# PAYL0003_PC_Memory.net
KiCad netlist of a schematic drawn in Altium Designer
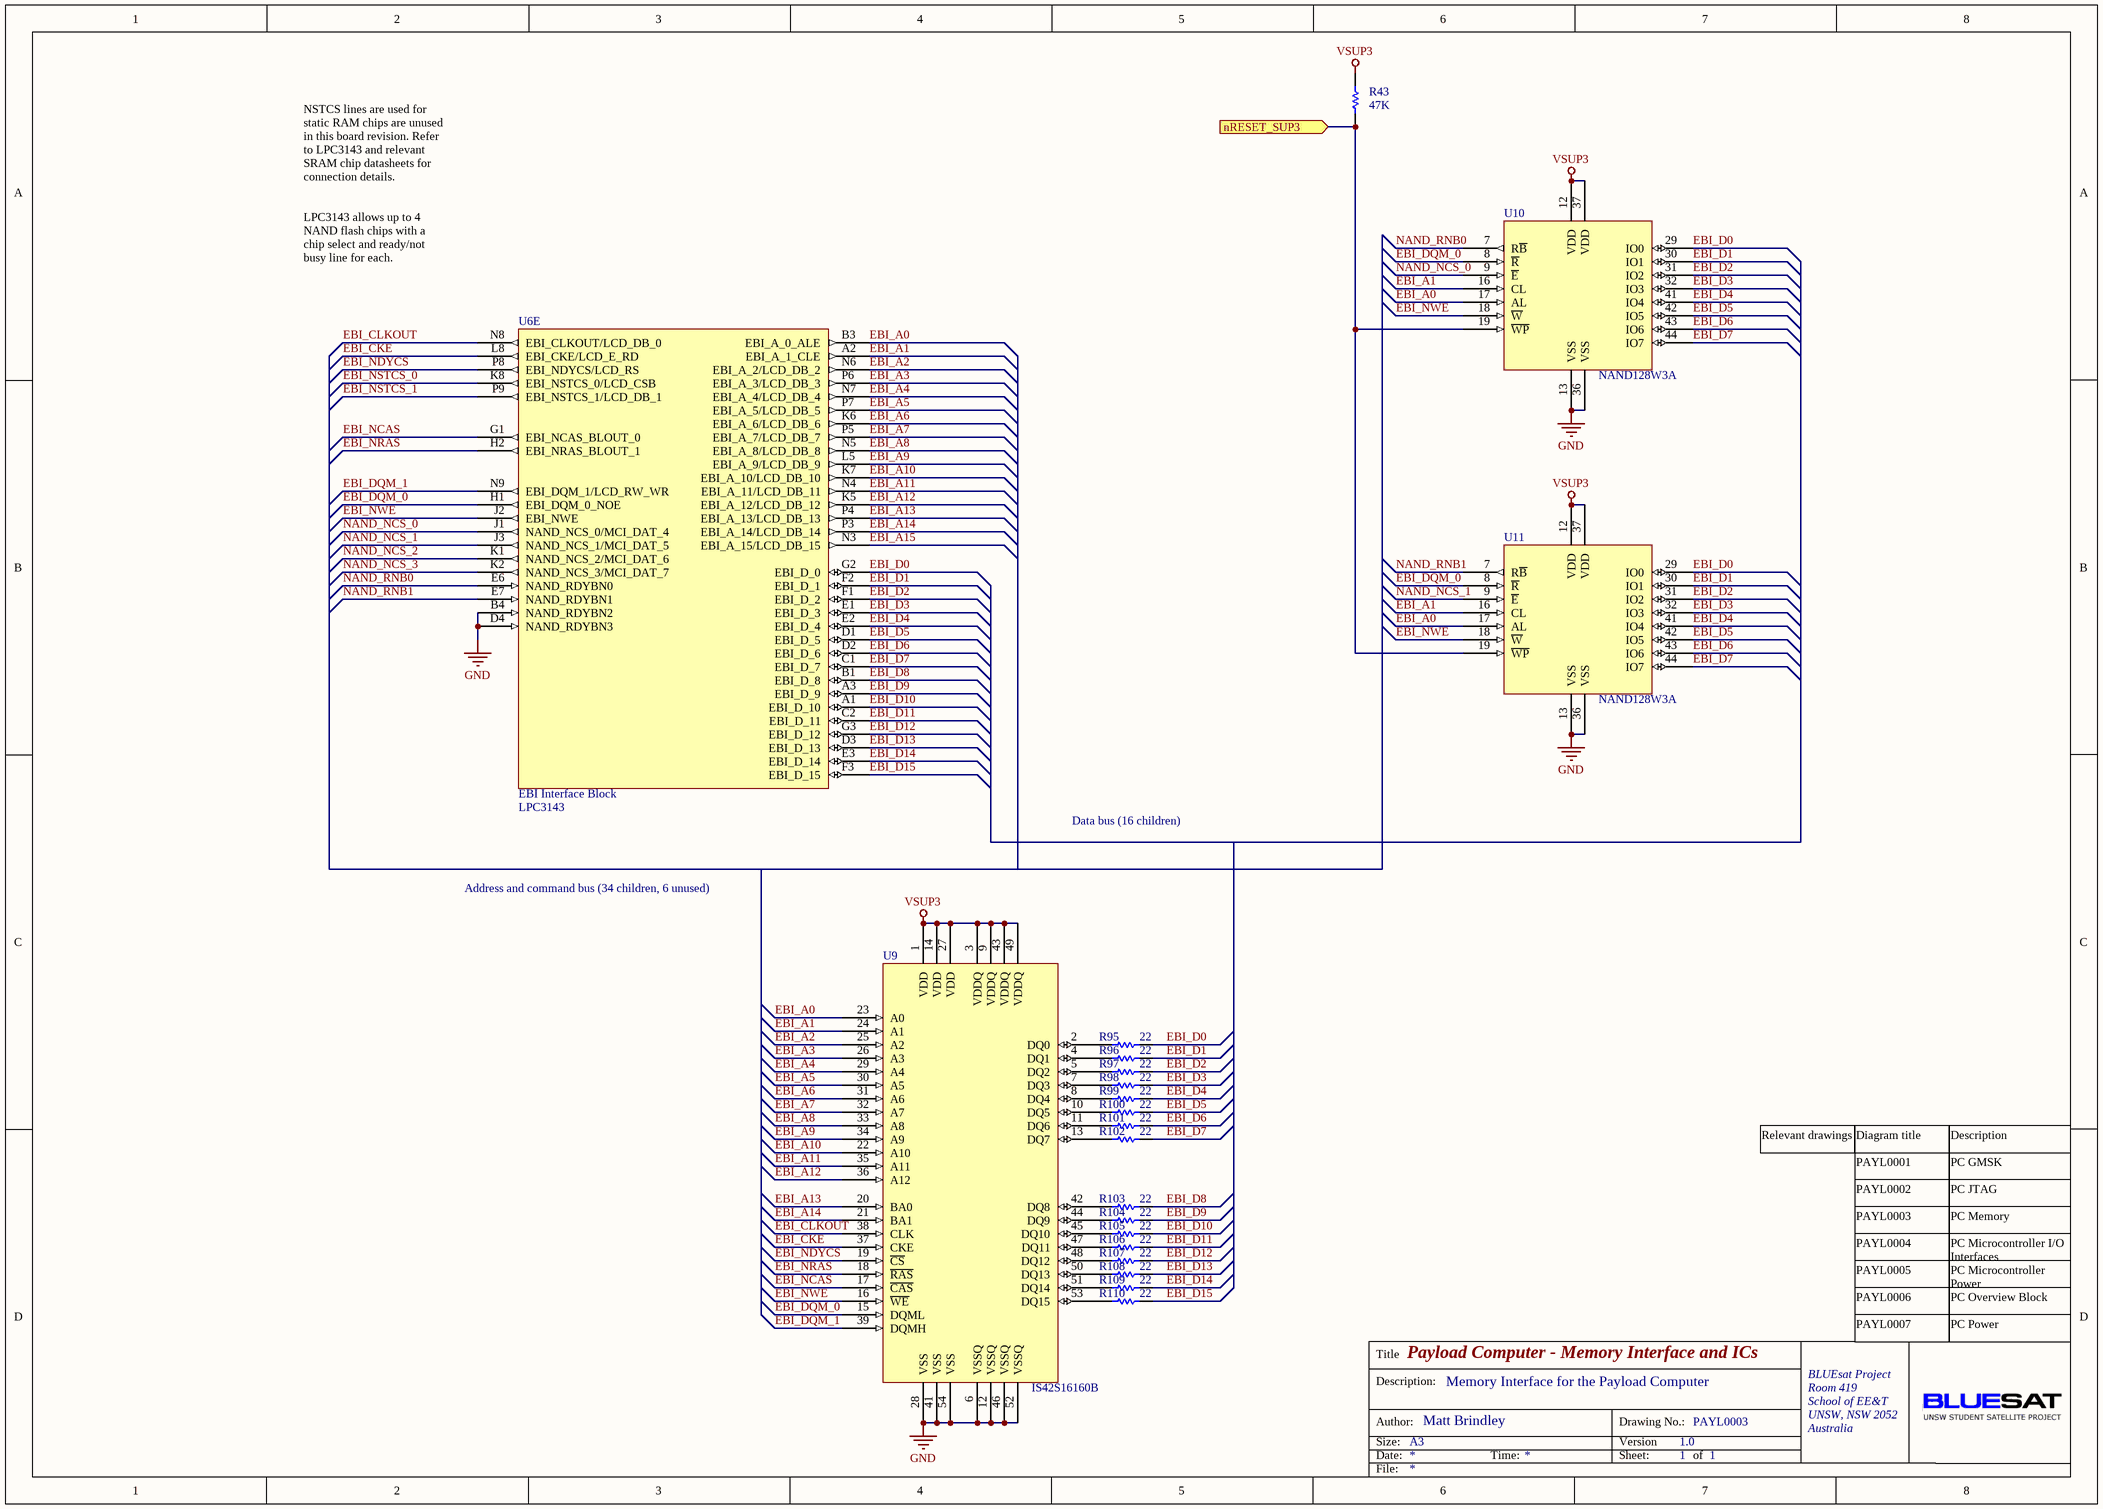
[diagram p0: PAYL0003_PC_Memory.SchDoc]

(export (version "E")
  (design (tool "Eeschema 10.0.6"))
  (components
    (comp (ref "R43")
      (value "47K")
      (footprint "6-0805_L")
      (description "Semiconductor Resistor")
      (fields (field (name "Comment") "Res Semi") (field (name "PUBLISHER") "Altium Limited"))
      (libsource (lib "Miscellaneous Devices") (part "Res Semi"))
    )
    (comp (ref "R95")
      (value "22")
      (footprint "6-0805_L")
      (description "Semiconductor Resistor")
      (fields (field (name "Comment") "Res Semi") (field (name "PUBLISHER") "Altium Limited"))
      (libsource (lib "Miscellaneous Devices") (part "Res Semi"))
    )
    (comp (ref "R96")
      (value "22")
      (footprint "6-0805_L")
      (description "Semiconductor Resistor")
      (fields (field (name "Comment") "Res Semi") (field (name "PUBLISHER") "Altium Limited"))
      (libsource (lib "Miscellaneous Devices") (part "Res Semi"))
    )
    (comp (ref "R97")
      (value "22")
      (footprint "6-0805_L")
      (description "Semiconductor Resistor")
      (fields (field (name "Comment") "Res Semi") (field (name "PUBLISHER") "Altium Limited"))
      (libsource (lib "Miscellaneous Devices") (part "Res Semi"))
    )
    (comp (ref "R98")
      (value "22")
      (footprint "6-0805_L")
      (description "Semiconductor Resistor")
      (fields (field (name "Comment") "Res Semi") (field (name "PUBLISHER") "Altium Limited"))
      (libsource (lib "Miscellaneous Devices") (part "Res Semi"))
    )
    (comp (ref "R99")
      (value "22")
      (footprint "6-0805_L")
      (description "Semiconductor Resistor")
      (fields (field (name "Comment") "Res Semi") (field (name "PUBLISHER") "Altium Limited"))
      (libsource (lib "Miscellaneous Devices") (part "Res Semi"))
    )
    (comp (ref "R100")
      (value "22")
      (footprint "6-0805_L")
      (description "Semiconductor Resistor")
      (fields (field (name "Comment") "Res Semi") (field (name "PUBLISHER") "Altium Limited"))
      (libsource (lib "Miscellaneous Devices") (part "Res Semi"))
    )
    (comp (ref "R101")
      (value "22")
      (footprint "6-0805_L")
      (description "Semiconductor Resistor")
      (fields (field (name "Comment") "Res Semi") (field (name "PUBLISHER") "Altium Limited"))
      (libsource (lib "Miscellaneous Devices") (part "Res Semi"))
    )
    (comp (ref "R102")
      (value "22")
      (footprint "6-0805_L")
      (description "Semiconductor Resistor")
      (fields (field (name "Comment") "Res Semi") (field (name "PUBLISHER") "Altium Limited"))
      (libsource (lib "Miscellaneous Devices") (part "Res Semi"))
    )
    (comp (ref "R103")
      (value "22")
      (footprint "6-0805_L")
      (description "Semiconductor Resistor")
      (fields (field (name "Comment") "Res Semi") (field (name "PUBLISHER") "Altium Limited"))
      (libsource (lib "Miscellaneous Devices") (part "Res Semi"))
    )
    (comp (ref "R104")
      (value "22")
      (footprint "6-0805_L")
      (description "Semiconductor Resistor")
      (fields (field (name "Comment") "Res Semi") (field (name "PUBLISHER") "Altium Limited"))
      (libsource (lib "Miscellaneous Devices") (part "Res Semi"))
    )
    (comp (ref "R105")
      (value "22")
      (footprint "6-0805_L")
      (description "Semiconductor Resistor")
      (fields (field (name "Comment") "Res Semi") (field (name "PUBLISHER") "Altium Limited"))
      (libsource (lib "Miscellaneous Devices") (part "Res Semi"))
    )
    (comp (ref "R106")
      (value "22")
      (footprint "6-0805_L")
      (description "Semiconductor Resistor")
      (fields (field (name "Comment") "Res Semi") (field (name "PUBLISHER") "Altium Limited"))
      (libsource (lib "Miscellaneous Devices") (part "Res Semi"))
    )
    (comp (ref "R107")
      (value "22")
      (footprint "6-0805_L")
      (description "Semiconductor Resistor")
      (fields (field (name "Comment") "Res Semi") (field (name "PUBLISHER") "Altium Limited"))
      (libsource (lib "Miscellaneous Devices") (part "Res Semi"))
    )
    (comp (ref "R108")
      (value "22")
      (footprint "6-0805_L")
      (description "Semiconductor Resistor")
      (fields (field (name "Comment") "Res Semi") (field (name "PUBLISHER") "Altium Limited"))
      (libsource (lib "Miscellaneous Devices") (part "Res Semi"))
    )
    (comp (ref "R109")
      (value "22")
      (footprint "6-0805_L")
      (description "Semiconductor Resistor")
      (fields (field (name "Comment") "Res Semi") (field (name "PUBLISHER") "Altium Limited"))
      (libsource (lib "Miscellaneous Devices") (part "Res Semi"))
    )
    (comp (ref "R110")
      (value "22")
      (footprint "6-0805_L")
      (description "Semiconductor Resistor")
      (fields (field (name "Comment") "Res Semi") (field (name "PUBLISHER") "Altium Limited"))
      (libsource (lib "Miscellaneous Devices") (part "Res Semi"))
    )
    (comp (ref "U6")
      (value "LPC3143")
      (footprint "PC_Footprints:BGA180C80P14X14_1200X1200X120")
      (description "NXP ARM9 based microcontroller")
      (fields (field (name "PUBLISHER") "BLUEsat Project"))
      (libsource (lib "PC_Components") (part "LPC3143"))
    )
    (comp (ref "U9")
      (value "IS42S16160B")
      (footprint "TSOP80P1180X120-54M")
      (description "16Mb x 16 (256Mb) Parallel Interface SDRAM")
      (fields (field (name "PUBLISHER") "Altium Limited"))
      (libsource (lib "PC_Components") (part "IS42S16160B"))
    )
    (comp (ref "U10")
      (value "NAND128W3A")
      (footprint "TSSOP50P2000X120-48M")
      (description "128Mb 8b wide NAND Flash")
      (fields (field (name "PUBLISHER") "Altium Limited"))
      (libsource (lib "PC_Components") (part "NAND128W3A"))
    )
    (comp (ref "U11")
      (value "NAND128W3A")
      (footprint "TSSOP50P2000X120-48M")
      (description "128Mb 8b wide NAND Flash")
      (fields (field (name "PUBLISHER") "Altium Limited"))
      (libsource (lib "PC_Components") (part "NAND128W3A"))
    )
  )
  (nets
    (net (code "1") (name "/EBI_A0") (class "Default")
      (node (ref "U10") (pin "17") (pinfunction "AL_17") (pintype "input"))
      (node (ref "U11") (pin "17") (pinfunction "AL_17") (pintype "input"))
      (node (ref "U6") (pin "B3") (pinfunction "EBI_A_0_ALE_B3") (pintype "output"))
      (node (ref "U9") (pin "23") (pinfunction "A0_23") (pintype "input"))
    )
    (net (code "2") (name "/EBI_A1") (class "Default")
      (node (ref "U10") (pin "16") (pinfunction "CL_16") (pintype "input"))
      (node (ref "U11") (pin "16") (pinfunction "CL_16") (pintype "input"))
      (node (ref "U6") (pin "A2") (pinfunction "EBI_A_1_CLE_A2") (pintype "output"))
      (node (ref "U9") (pin "24") (pinfunction "A1_24") (pintype "input"))
    )
    (net (code "3") (name "/EBI_A2") (class "Default")
      (node (ref "U6") (pin "N6") (pinfunction "EBI_A_2/LCD_DB_2_N6") (pintype "output"))
      (node (ref "U9") (pin "25") (pinfunction "A2_25") (pintype "input"))
    )
    (net (code "4") (name "/EBI_A3") (class "Default")
      (node (ref "U6") (pin "P6") (pinfunction "EBI_A_3/LCD_DB_3_P6") (pintype "output"))
      (node (ref "U9") (pin "26") (pinfunction "A3_26") (pintype "input"))
    )
    (net (code "5") (name "/EBI_A4") (class "Default")
      (node (ref "U6") (pin "N7") (pinfunction "EBI_A_4/LCD_DB_4_N7") (pintype "output"))
      (node (ref "U9") (pin "29") (pinfunction "A4_29") (pintype "input"))
    )
    (net (code "6") (name "/EBI_A5") (class "Default")
      (node (ref "U6") (pin "P7") (pinfunction "EBI_A_5/LCD_DB_5_P7") (pintype "output"))
      (node (ref "U9") (pin "30") (pinfunction "A5_30") (pintype "input"))
    )
    (net (code "7") (name "/EBI_A6") (class "Default")
      (node (ref "U6") (pin "K6") (pinfunction "EBI_A_6/LCD_DB_6_K6") (pintype "output"))
      (node (ref "U9") (pin "31") (pinfunction "A6_31") (pintype "input"))
    )
    (net (code "8") (name "/EBI_A7") (class "Default")
      (node (ref "U6") (pin "P5") (pinfunction "EBI_A_7/LCD_DB_7_P5") (pintype "output"))
      (node (ref "U9") (pin "32") (pinfunction "A7_32") (pintype "input"))
    )
    (net (code "9") (name "/EBI_A8") (class "Default")
      (node (ref "U6") (pin "N5") (pinfunction "EBI_A_8/LCD_DB_8_N5") (pintype "output"))
      (node (ref "U9") (pin "33") (pinfunction "A8_33") (pintype "input"))
    )
    (net (code "10") (name "/EBI_A9") (class "Default")
      (node (ref "U6") (pin "L5") (pinfunction "EBI_A_9/LCD_DB_9_L5") (pintype "output"))
      (node (ref "U9") (pin "34") (pinfunction "A9_34") (pintype "input"))
    )
    (net (code "11") (name "/EBI_A10") (class "Default")
      (node (ref "U6") (pin "K7") (pinfunction "EBI_A_10/LCD_DB_10_K7") (pintype "output"))
      (node (ref "U9") (pin "22") (pinfunction "A10_22") (pintype "input"))
    )
    (net (code "12") (name "/EBI_A11") (class "Default")
      (node (ref "U6") (pin "N4") (pinfunction "EBI_A_11/LCD_DB_11_N4") (pintype "output"))
      (node (ref "U9") (pin "35") (pinfunction "A11_35") (pintype "input"))
    )
    (net (code "13") (name "/EBI_A12") (class "Default")
      (node (ref "U6") (pin "K5") (pinfunction "EBI_A_12/LCD_DB_12_K5") (pintype "output"))
      (node (ref "U9") (pin "36") (pinfunction "A12_36") (pintype "input"))
    )
    (net (code "14") (name "/EBI_A13") (class "Default")
      (node (ref "U6") (pin "P4") (pinfunction "EBI_A_13/LCD_DB_13_P4") (pintype "output"))
      (node (ref "U9") (pin "20") (pinfunction "BA0_20") (pintype "input"))
    )
    (net (code "15") (name "/EBI_A14") (class "Default")
      (node (ref "U6") (pin "P3") (pinfunction "EBI_A_14/LCD_DB_14_P3") (pintype "output"))
      (node (ref "U9") (pin "21") (pinfunction "BA1_21") (pintype "input"))
    )
    (net (code "16") (name "/EBI_A15") (class "Default")
      (node (ref "U6") (pin "N3") (pinfunction "EBI_A_15/LCD_DB_15_N3") (pintype "output"))
    )
    (net (code "17") (name "/EBI_CKE") (class "Default")
      (node (ref "U6") (pin "L8") (pinfunction "EBI_CKE/LCD_E_RD_L8") (pintype "output"))
      (node (ref "U9") (pin "37") (pinfunction "CKE_37") (pintype "input"))
    )
    (net (code "18") (name "/EBI_CLKOUT") (class "Default")
      (node (ref "U6") (pin "N8") (pinfunction "EBI_CLKOUT/LCD_DB_0_N8") (pintype "output"))
      (node (ref "U9") (pin "38") (pinfunction "CLK_38") (pintype "input"))
    )
    (net (code "19") (name "/EBI_D0") (class "Default")
      (node (ref "R95") (pin "2") (pinfunction "2_2") (pintype "passive"))
      (node (ref "U10") (pin "29") (pinfunction "IO0_29") (pintype "bidirectional"))
      (node (ref "U11") (pin "29") (pinfunction "IO0_29") (pintype "bidirectional"))
      (node (ref "U6") (pin "G2") (pinfunction "EBI_D_0_G2") (pintype "bidirectional"))
    )
    (net (code "20") (name "/EBI_D1") (class "Default")
      (node (ref "R96") (pin "2") (pinfunction "2_2") (pintype "passive"))
      (node (ref "U10") (pin "30") (pinfunction "IO1_30") (pintype "bidirectional"))
      (node (ref "U11") (pin "30") (pinfunction "IO1_30") (pintype "bidirectional"))
      (node (ref "U6") (pin "F2") (pinfunction "EBI_D_1_F2") (pintype "bidirectional"))
    )
    (net (code "21") (name "/EBI_D2") (class "Default")
      (node (ref "R97") (pin "2") (pinfunction "2_2") (pintype "passive"))
      (node (ref "U10") (pin "31") (pinfunction "IO2_31") (pintype "bidirectional"))
      (node (ref "U11") (pin "31") (pinfunction "IO2_31") (pintype "bidirectional"))
      (node (ref "U6") (pin "F1") (pinfunction "EBI_D_2_F1") (pintype "bidirectional"))
    )
    (net (code "22") (name "/EBI_D3") (class "Default")
      (node (ref "R98") (pin "2") (pinfunction "2_2") (pintype "passive"))
      (node (ref "U10") (pin "32") (pinfunction "IO3_32") (pintype "bidirectional"))
      (node (ref "U11") (pin "32") (pinfunction "IO3_32") (pintype "bidirectional"))
      (node (ref "U6") (pin "E1") (pinfunction "EBI_D_3_E1") (pintype "bidirectional"))
    )
    (net (code "23") (name "/EBI_D4") (class "Default")
      (node (ref "R99") (pin "2") (pinfunction "2_2") (pintype "passive"))
      (node (ref "U10") (pin "41") (pinfunction "IO4_41") (pintype "bidirectional"))
      (node (ref "U11") (pin "41") (pinfunction "IO4_41") (pintype "bidirectional"))
      (node (ref "U6") (pin "E2") (pinfunction "EBI_D_4_E2") (pintype "bidirectional"))
    )
    (net (code "24") (name "/EBI_D5") (class "Default")
      (node (ref "R100") (pin "2") (pinfunction "2_2") (pintype "passive"))
      (node (ref "U10") (pin "42") (pinfunction "IO5_42") (pintype "bidirectional"))
      (node (ref "U11") (pin "42") (pinfunction "IO5_42") (pintype "bidirectional"))
      (node (ref "U6") (pin "D1") (pinfunction "EBI_D_5_D1") (pintype "bidirectional"))
    )
    (net (code "25") (name "/EBI_D6") (class "Default")
      (node (ref "R101") (pin "2") (pinfunction "2_2") (pintype "passive"))
      (node (ref "U10") (pin "43") (pinfunction "IO6_43") (pintype "bidirectional"))
      (node (ref "U11") (pin "43") (pinfunction "IO6_43") (pintype "bidirectional"))
      (node (ref "U6") (pin "D2") (pinfunction "EBI_D_6_D2") (pintype "bidirectional"))
    )
    (net (code "26") (name "/EBI_D7") (class "Default")
      (node (ref "R102") (pin "2") (pinfunction "2_2") (pintype "passive"))
      (node (ref "U10") (pin "44") (pinfunction "IO7_44") (pintype "bidirectional"))
      (node (ref "U11") (pin "44") (pinfunction "IO7_44") (pintype "bidirectional"))
      (node (ref "U6") (pin "C1") (pinfunction "EBI_D_7_C1") (pintype "bidirectional"))
    )
    (net (code "27") (name "/EBI_D8") (class "Default")
      (node (ref "R103") (pin "2") (pinfunction "2_2") (pintype "passive"))
      (node (ref "U6") (pin "B1") (pinfunction "EBI_D_8_B1") (pintype "bidirectional"))
    )
    (net (code "28") (name "/EBI_D9") (class "Default")
      (node (ref "R104") (pin "2") (pinfunction "2_2") (pintype "passive"))
      (node (ref "U6") (pin "A3") (pinfunction "EBI_D_9_A3") (pintype "bidirectional"))
    )
    (net (code "29") (name "/EBI_D10") (class "Default")
      (node (ref "R105") (pin "2") (pinfunction "2_2") (pintype "passive"))
      (node (ref "U6") (pin "A1") (pinfunction "EBI_D_10_A1") (pintype "bidirectional"))
    )
    (net (code "30") (name "/EBI_D11") (class "Default")
      (node (ref "R106") (pin "2") (pinfunction "2_2") (pintype "passive"))
      (node (ref "U6") (pin "C2") (pinfunction "EBI_D_11_C2") (pintype "bidirectional"))
    )
    (net (code "31") (name "/EBI_D12") (class "Default")
      (node (ref "R107") (pin "2") (pinfunction "2_2") (pintype "passive"))
      (node (ref "U6") (pin "G3") (pinfunction "EBI_D_12_G3") (pintype "bidirectional"))
    )
    (net (code "32") (name "/EBI_D13") (class "Default")
      (node (ref "R108") (pin "2") (pinfunction "2_2") (pintype "passive"))
      (node (ref "U6") (pin "D3") (pinfunction "EBI_D_13_D3") (pintype "bidirectional"))
    )
    (net (code "33") (name "/EBI_D14") (class "Default")
      (node (ref "R109") (pin "2") (pinfunction "2_2") (pintype "passive"))
      (node (ref "U6") (pin "E3") (pinfunction "EBI_D_14_E3") (pintype "bidirectional"))
    )
    (net (code "34") (name "/EBI_D15") (class "Default")
      (node (ref "R110") (pin "2") (pinfunction "2_2") (pintype "passive"))
      (node (ref "U6") (pin "F3") (pinfunction "EBI_D_15_F3") (pintype "bidirectional"))
    )
    (net (code "35") (name "/EBI_DQM_0") (class "Default")
      (node (ref "U10") (pin "8") (pinfunction "~{R}_8") (pintype "input"))
      (node (ref "U11") (pin "8") (pinfunction "~{R}_8") (pintype "input"))
      (node (ref "U6") (pin "H1") (pinfunction "EBI_DQM_0_NOE_H1") (pintype "output"))
      (node (ref "U9") (pin "15") (pinfunction "DQML_15") (pintype "input"))
    )
    (net (code "36") (name "/EBI_DQM_1") (class "Default")
      (node (ref "U6") (pin "N9") (pinfunction "EBI_DQM_1/LCD_RW_WR_N9") (pintype "output"))
      (node (ref "U9") (pin "39") (pinfunction "DQMH_39") (pintype "input"))
    )
    (net (code "37") (name "/EBI_NCAS") (class "Default")
      (node (ref "U6") (pin "G1") (pinfunction "EBI_NCAS_BLOUT_0_G1") (pintype "output"))
      (node (ref "U9") (pin "17") (pinfunction "~{CAS}_17") (pintype "input"))
    )
    (net (code "38") (name "/EBI_NDYCS") (class "Default")
      (node (ref "U6") (pin "P8") (pinfunction "EBI_NDYCS/LCD_RS_P8") (pintype "output"))
      (node (ref "U9") (pin "19") (pinfunction "~{CS}_19") (pintype "input"))
    )
    (net (code "39") (name "/EBI_NRAS") (class "Default")
      (node (ref "U6") (pin "H2") (pinfunction "EBI_NRAS_BLOUT_1_H2") (pintype "output"))
      (node (ref "U9") (pin "18") (pinfunction "~{RAS}_18") (pintype "input"))
    )
    (net (code "40") (name "/EBI_NSTCS_0") (class "Default")
      (node (ref "U6") (pin "K8") (pinfunction "EBI_NSTCS_0/LCD_CSB_K8") (pintype "output"))
    )
    (net (code "41") (name "/EBI_NSTCS_1") (class "Default")
      (node (ref "U6") (pin "P9") (pinfunction "EBI_NSTCS_1/LCD_DB_1_P9") (pintype "output"))
    )
    (net (code "42") (name "/EBI_NWE") (class "Default")
      (node (ref "U10") (pin "18") (pinfunction "~{W}_18") (pintype "input"))
      (node (ref "U11") (pin "18") (pinfunction "~{W}_18") (pintype "input"))
      (node (ref "U6") (pin "J2") (pinfunction "EBI_NWE_J2") (pintype "output"))
      (node (ref "U9") (pin "16") (pinfunction "~{WE}_16") (pintype "input"))
    )
    (net (code "43") (name "/NAND_NCS_0") (class "Default")
      (node (ref "U10") (pin "9") (pinfunction "~{E}_9") (pintype "input"))
      (node (ref "U6") (pin "J1") (pinfunction "NAND_NCS_0/MCI_DAT_4_J1") (pintype "output"))
    )
    (net (code "44") (name "/NAND_NCS_1") (class "Default")
      (node (ref "U11") (pin "9") (pinfunction "~{E}_9") (pintype "input"))
      (node (ref "U6") (pin "J3") (pinfunction "NAND_NCS_1/MCI_DAT_5_J3") (pintype "output"))
    )
    (net (code "45") (name "/NAND_NCS_2") (class "Default")
      (node (ref "U6") (pin "K1") (pinfunction "NAND_NCS_2/MCI_DAT_6_K1") (pintype "output"))
    )
    (net (code "46") (name "/NAND_NCS_3") (class "Default")
      (node (ref "U6") (pin "K2") (pinfunction "NAND_NCS_3/MCI_DAT_7_K2") (pintype "output"))
    )
    (net (code "47") (name "/NAND_RNB0") (class "Default")
      (node (ref "U10") (pin "7") (pinfunction "R~{B}_7") (pintype "output"))
      (node (ref "U6") (pin "E6") (pinfunction "NAND_RDYBN0_E6") (pintype "input"))
    )
    (net (code "48") (name "/NAND_RNB1") (class "Default")
      (node (ref "U11") (pin "7") (pinfunction "R~{B}_7") (pintype "output"))
      (node (ref "U6") (pin "E7") (pinfunction "NAND_RDYBN1_E7") (pintype "input"))
    )
    (net (code "49") (name "/nRESET_SUP3") (class "Default")
      (node (ref "R43") (pin "1") (pinfunction "1_1") (pintype "passive"))
      (node (ref "U10") (pin "19") (pinfunction "~{WP}_19") (pintype "input"))
      (node (ref "U11") (pin "19") (pinfunction "~{WP}_19") (pintype "input"))
    )
    (net (code "50") (name "GND") (class "Default")
      (node (ref "U10") (pin "13") (pinfunction "VSS_13") (pintype "power_in"))
      (node (ref "U10") (pin "36") (pinfunction "VSS_36") (pintype "power_in"))
      (node (ref "U11") (pin "13") (pinfunction "VSS_13") (pintype "power_in"))
      (node (ref "U11") (pin "36") (pinfunction "VSS_36") (pintype "power_in"))
      (node (ref "U6") (pin "B4") (pinfunction "NAND_RDYBN2_B4") (pintype "input"))
      (node (ref "U6") (pin "D4") (pinfunction "NAND_RDYBN3_D4") (pintype "input"))
      (node (ref "U9") (pin "12") (pinfunction "VSSQ_12") (pintype "power_in"))
      (node (ref "U9") (pin "28") (pinfunction "VSS_28") (pintype "power_in"))
      (node (ref "U9") (pin "41") (pinfunction "VSS_41") (pintype "power_in"))
      (node (ref "U9") (pin "46") (pinfunction "VSSQ_46") (pintype "power_in"))
      (node (ref "U9") (pin "52") (pinfunction "VSSQ_52") (pintype "power_in"))
      (node (ref "U9") (pin "54") (pinfunction "VSS_54") (pintype "power_in"))
      (node (ref "U9") (pin "6") (pinfunction "VSSQ_6") (pintype "power_in"))
    )
    (net (code "51") (name "Net-(U9-DQ0)") (class "Default")
      (node (ref "R95") (pin "1") (pinfunction "1_1") (pintype "passive"))
      (node (ref "U9") (pin "2") (pinfunction "DQ0_2") (pintype "bidirectional"))
    )
    (net (code "52") (name "Net-(U9-DQ1)") (class "Default")
      (node (ref "R96") (pin "1") (pinfunction "1_1") (pintype "passive"))
      (node (ref "U9") (pin "4") (pinfunction "DQ1_4") (pintype "bidirectional"))
    )
    (net (code "53") (name "Net-(U9-DQ2)") (class "Default")
      (node (ref "R97") (pin "1") (pinfunction "1_1") (pintype "passive"))
      (node (ref "U9") (pin "5") (pinfunction "DQ2_5") (pintype "bidirectional"))
    )
    (net (code "54") (name "Net-(U9-DQ3)") (class "Default")
      (node (ref "R98") (pin "1") (pinfunction "1_1") (pintype "passive"))
      (node (ref "U9") (pin "7") (pinfunction "DQ3_7") (pintype "bidirectional"))
    )
    (net (code "55") (name "Net-(U9-DQ4)") (class "Default")
      (node (ref "R99") (pin "1") (pinfunction "1_1") (pintype "passive"))
      (node (ref "U9") (pin "8") (pinfunction "DQ4_8") (pintype "bidirectional"))
    )
    (net (code "56") (name "Net-(U9-DQ5)") (class "Default")
      (node (ref "R100") (pin "1") (pinfunction "1_1") (pintype "passive"))
      (node (ref "U9") (pin "10") (pinfunction "DQ5_10") (pintype "bidirectional"))
    )
    (net (code "57") (name "Net-(U9-DQ6)") (class "Default")
      (node (ref "R101") (pin "1") (pinfunction "1_1") (pintype "passive"))
      (node (ref "U9") (pin "11") (pinfunction "DQ6_11") (pintype "bidirectional"))
    )
    (net (code "58") (name "Net-(U9-DQ7)") (class "Default")
      (node (ref "R102") (pin "1") (pinfunction "1_1") (pintype "passive"))
      (node (ref "U9") (pin "13") (pinfunction "DQ7_13") (pintype "bidirectional"))
    )
    (net (code "59") (name "Net-(U9-DQ8)") (class "Default")
      (node (ref "R103") (pin "1") (pinfunction "1_1") (pintype "passive"))
      (node (ref "U9") (pin "42") (pinfunction "DQ8_42") (pintype "bidirectional"))
    )
    (net (code "60") (name "Net-(U9-DQ9)") (class "Default")
      (node (ref "R104") (pin "1") (pinfunction "1_1") (pintype "passive"))
      (node (ref "U9") (pin "44") (pinfunction "DQ9_44") (pintype "bidirectional"))
    )
    (net (code "61") (name "Net-(U9-DQ10)") (class "Default")
      (node (ref "R105") (pin "1") (pinfunction "1_1") (pintype "passive"))
      (node (ref "U9") (pin "45") (pinfunction "DQ10_45") (pintype "bidirectional"))
    )
    (net (code "62") (name "Net-(U9-DQ11)") (class "Default")
      (node (ref "R106") (pin "1") (pinfunction "1_1") (pintype "passive"))
      (node (ref "U9") (pin "47") (pinfunction "DQ11_47") (pintype "bidirectional"))
    )
    (net (code "63") (name "Net-(U9-DQ12)") (class "Default")
      (node (ref "R107") (pin "1") (pinfunction "1_1") (pintype "passive"))
      (node (ref "U9") (pin "48") (pinfunction "DQ12_48") (pintype "bidirectional"))
    )
    (net (code "64") (name "Net-(U9-DQ13)") (class "Default")
      (node (ref "R108") (pin "1") (pinfunction "1_1") (pintype "passive"))
      (node (ref "U9") (pin "50") (pinfunction "DQ13_50") (pintype "bidirectional"))
    )
    (net (code "65") (name "Net-(U9-DQ14)") (class "Default")
      (node (ref "R109") (pin "1") (pinfunction "1_1") (pintype "passive"))
      (node (ref "U9") (pin "51") (pinfunction "DQ14_51") (pintype "bidirectional"))
    )
    (net (code "66") (name "Net-(U9-DQ15)") (class "Default")
      (node (ref "R110") (pin "1") (pinfunction "1_1") (pintype "passive"))
      (node (ref "U9") (pin "53") (pinfunction "DQ15_53") (pintype "bidirectional"))
    )
    (net (code "67") (name "VSUP3") (class "Default")
      (node (ref "R43") (pin "2") (pinfunction "2_2") (pintype "passive"))
      (node (ref "U10") (pin "12") (pinfunction "VDD_12") (pintype "power_in"))
      (node (ref "U10") (pin "37") (pinfunction "VDD_37") (pintype "power_in"))
      (node (ref "U11") (pin "12") (pinfunction "VDD_12") (pintype "power_in"))
      (node (ref "U11") (pin "37") (pinfunction "VDD_37") (pintype "power_in"))
      (node (ref "U9") (pin "1") (pinfunction "VDD_1") (pintype "power_in"))
      (node (ref "U9") (pin "14") (pinfunction "VDD_14") (pintype "power_in"))
      (node (ref "U9") (pin "27") (pinfunction "VDD_27") (pintype "power_in"))
      (node (ref "U9") (pin "3") (pinfunction "VDDQ_3") (pintype "power_in"))
      (node (ref "U9") (pin "43") (pinfunction "VDDQ_43") (pintype "power_in"))
      (node (ref "U9") (pin "49") (pinfunction "VDDQ_49") (pintype "power_in"))
      (node (ref "U9") (pin "9") (pinfunction "VDDQ_9") (pintype "power_in"))
    )
  )
)
